# TEK-8x8.net
KiCad netlist of a schematic drawn in EAGLE
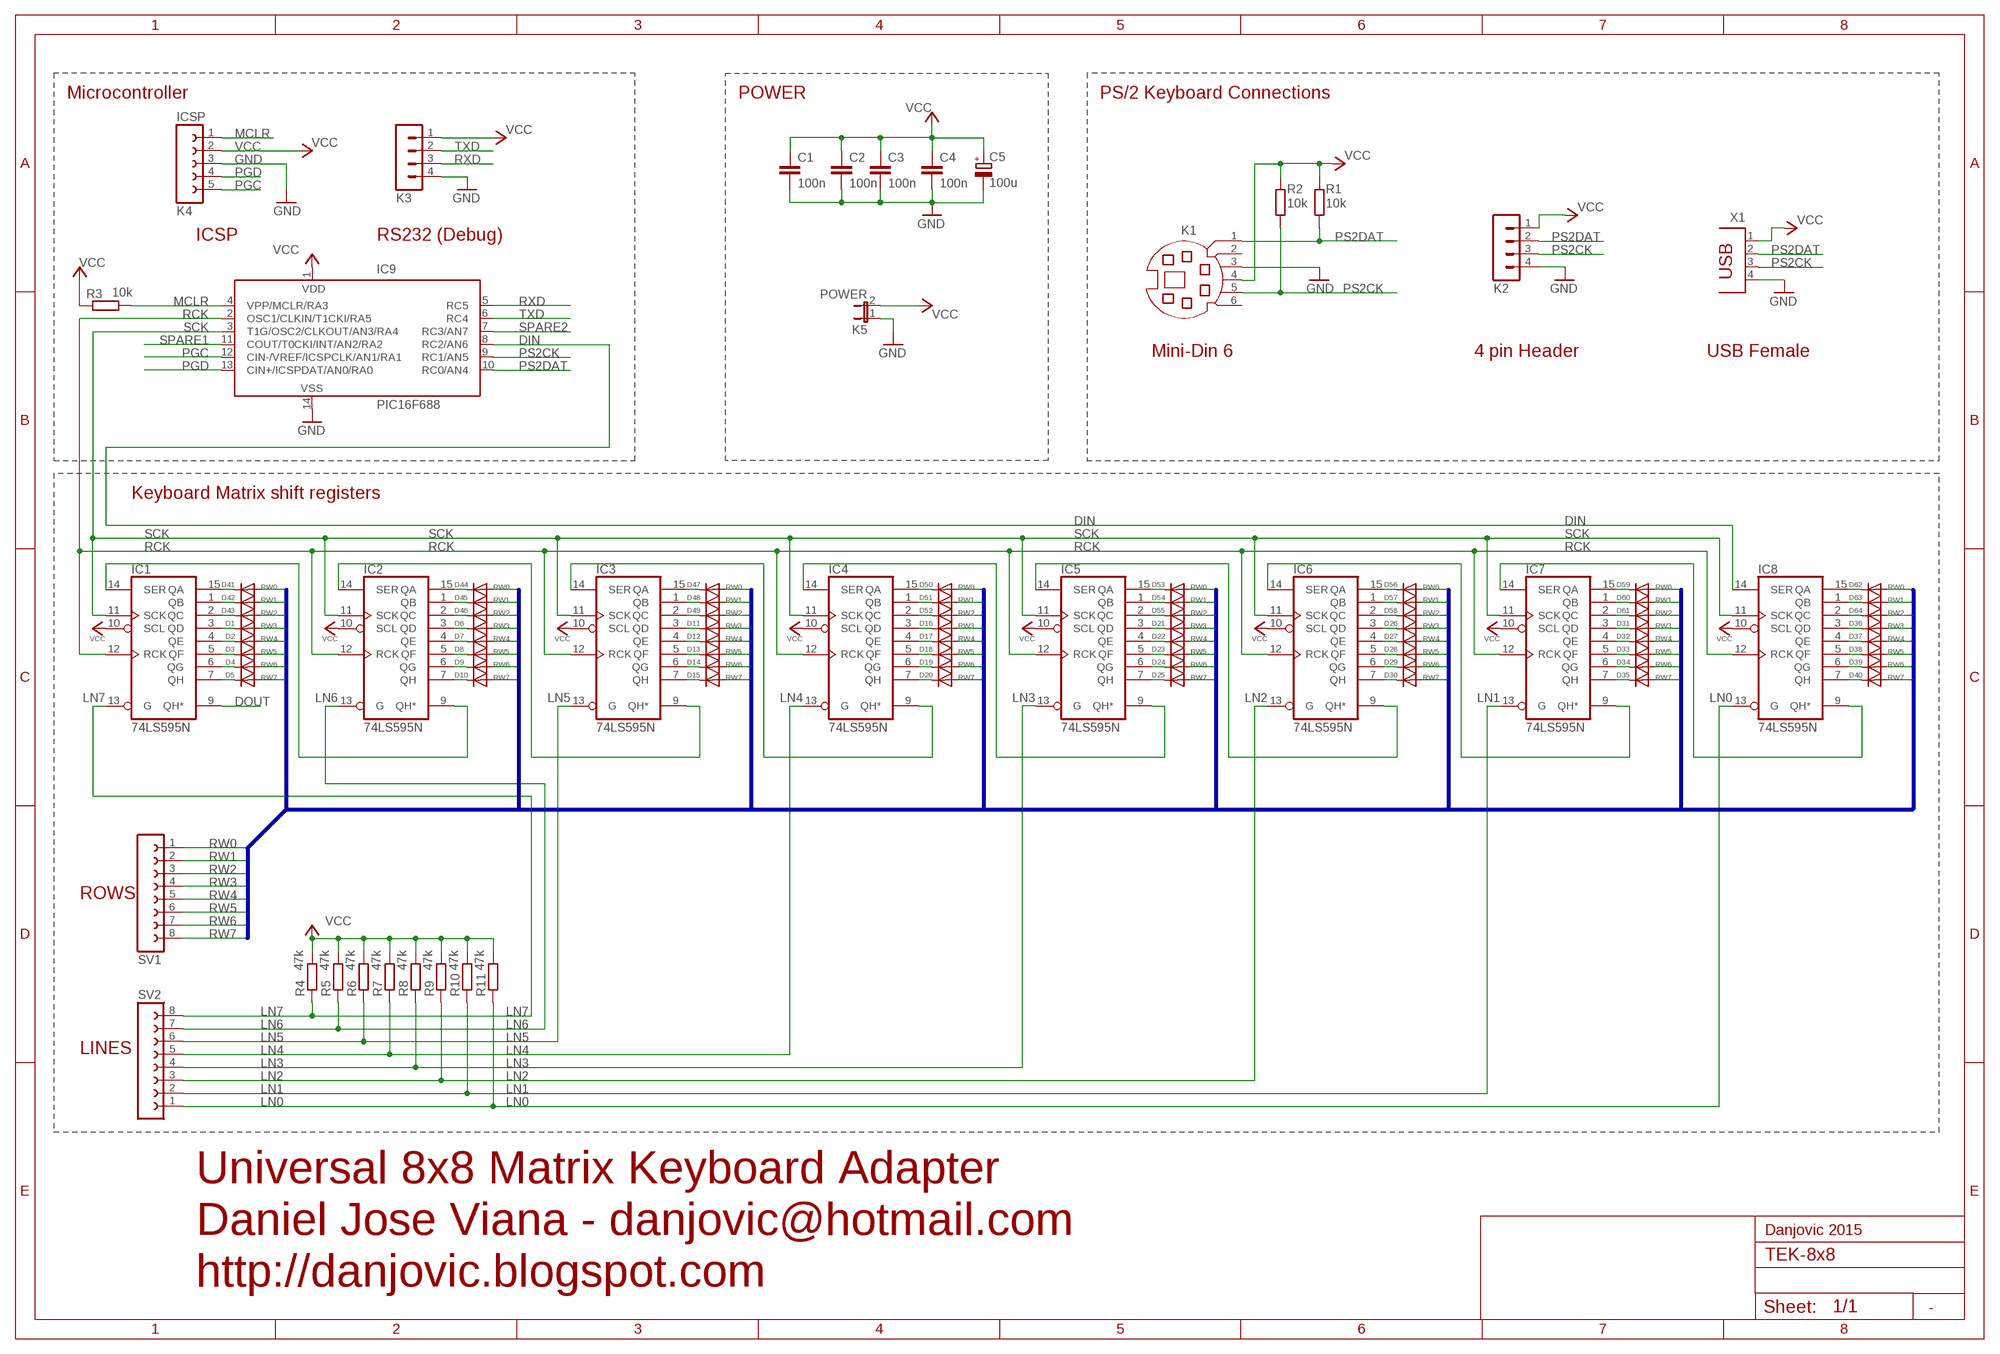
[diagram p0: schematic, sheet 1]

(export (version "E")
  (design (tool "Eeschema 10.0.6"))
  (components
    (comp (ref "C1")
      (value "100n")
      (footprint "eagle-import:C050-030X075")
      (libsource (lib "eagle-import") (part "C-EU050-030X075"))
    )
    (comp (ref "C2")
      (value "100n")
      (footprint "eagle-import:C050-030X075")
      (libsource (lib "eagle-import") (part "C-EU050-030X075"))
    )
    (comp (ref "C3")
      (value "100n")
      (footprint "eagle-import:C050-030X075")
      (libsource (lib "eagle-import") (part "C-EU050-030X075"))
    )
    (comp (ref "C4")
      (value "100n")
      (footprint "eagle-import:C050-030X075")
      (libsource (lib "eagle-import") (part "C-EU050-030X075"))
    )
    (comp (ref "C5")
      (value "100u")
      (footprint "eagle-import:E3,5-10")
      (libsource (lib "eagle-import") (part "CPOL-EUE3.5-10"))
    )
    (comp (ref "D1")
      (value "DIODE-D-2.5")
      (footprint "eagle-import:D-2.5")
      (libsource (lib "eagle-import") (part "DIODE-D-2.5"))
    )
    (comp (ref "D2")
      (value "DIODE-D-2.5")
      (footprint "eagle-import:D-2.5")
      (libsource (lib "eagle-import") (part "DIODE-D-2.5"))
    )
    (comp (ref "D3")
      (value "DIODE-D-2.5")
      (footprint "eagle-import:D-2.5")
      (libsource (lib "eagle-import") (part "DIODE-D-2.5"))
    )
    (comp (ref "D4")
      (value "DIODE-D-2.5")
      (footprint "eagle-import:D-2.5")
      (libsource (lib "eagle-import") (part "DIODE-D-2.5"))
    )
    (comp (ref "D5")
      (value "DIODE-D-2.5")
      (footprint "eagle-import:D-2.5")
      (libsource (lib "eagle-import") (part "DIODE-D-2.5"))
    )
    (comp (ref "D6")
      (value "DIODE-D-2.5")
      (footprint "eagle-import:D-2.5")
      (libsource (lib "eagle-import") (part "DIODE-D-2.5"))
    )
    (comp (ref "D7")
      (value "DIODE-D-2.5")
      (footprint "eagle-import:D-2.5")
      (libsource (lib "eagle-import") (part "DIODE-D-2.5"))
    )
    (comp (ref "D8")
      (value "DIODE-D-2.5")
      (footprint "eagle-import:D-2.5")
      (libsource (lib "eagle-import") (part "DIODE-D-2.5"))
    )
    (comp (ref "D9")
      (value "DIODE-D-2.5")
      (footprint "eagle-import:D-2.5")
      (libsource (lib "eagle-import") (part "DIODE-D-2.5"))
    )
    (comp (ref "D10")
      (value "DIODE-D-2.5")
      (footprint "eagle-import:D-2.5")
      (libsource (lib "eagle-import") (part "DIODE-D-2.5"))
    )
    (comp (ref "D11")
      (value "DIODE-D-2.5")
      (footprint "eagle-import:D-2.5")
      (libsource (lib "eagle-import") (part "DIODE-D-2.5"))
    )
    (comp (ref "D12")
      (value "DIODE-D-2.5")
      (footprint "eagle-import:D-2.5")
      (libsource (lib "eagle-import") (part "DIODE-D-2.5"))
    )
    (comp (ref "D13")
      (value "DIODE-D-2.5")
      (footprint "eagle-import:D-2.5")
      (libsource (lib "eagle-import") (part "DIODE-D-2.5"))
    )
    (comp (ref "D14")
      (value "DIODE-D-2.5")
      (footprint "eagle-import:D-2.5")
      (libsource (lib "eagle-import") (part "DIODE-D-2.5"))
    )
    (comp (ref "D15")
      (value "DIODE-D-2.5")
      (footprint "eagle-import:D-2.5")
      (libsource (lib "eagle-import") (part "DIODE-D-2.5"))
    )
    (comp (ref "D16")
      (value "DIODE-D-2.5")
      (footprint "eagle-import:D-2.5")
      (libsource (lib "eagle-import") (part "DIODE-D-2.5"))
    )
    (comp (ref "D17")
      (value "DIODE-D-2.5")
      (footprint "eagle-import:D-2.5")
      (libsource (lib "eagle-import") (part "DIODE-D-2.5"))
    )
    (comp (ref "D18")
      (value "DIODE-D-2.5")
      (footprint "eagle-import:D-2.5")
      (libsource (lib "eagle-import") (part "DIODE-D-2.5"))
    )
    (comp (ref "D19")
      (value "DIODE-D-2.5")
      (footprint "eagle-import:D-2.5")
      (libsource (lib "eagle-import") (part "DIODE-D-2.5"))
    )
    (comp (ref "D20")
      (value "DIODE-D-2.5")
      (footprint "eagle-import:D-2.5")
      (libsource (lib "eagle-import") (part "DIODE-D-2.5"))
    )
    (comp (ref "D21")
      (value "DIODE-D-2.5")
      (footprint "eagle-import:D-2.5")
      (libsource (lib "eagle-import") (part "DIODE-D-2.5"))
    )
    (comp (ref "D22")
      (value "DIODE-D-2.5")
      (footprint "eagle-import:D-2.5")
      (libsource (lib "eagle-import") (part "DIODE-D-2.5"))
    )
    (comp (ref "D23")
      (value "DIODE-D-2.5")
      (footprint "eagle-import:D-2.5")
      (libsource (lib "eagle-import") (part "DIODE-D-2.5"))
    )
    (comp (ref "D24")
      (value "DIODE-D-2.5")
      (footprint "eagle-import:D-2.5")
      (libsource (lib "eagle-import") (part "DIODE-D-2.5"))
    )
    (comp (ref "D25")
      (value "DIODE-D-2.5")
      (footprint "eagle-import:D-2.5")
      (libsource (lib "eagle-import") (part "DIODE-D-2.5"))
    )
    (comp (ref "D26")
      (value "DIODE-D-2.5")
      (footprint "eagle-import:D-2.5")
      (libsource (lib "eagle-import") (part "DIODE-D-2.5"))
    )
    (comp (ref "D27")
      (value "DIODE-D-2.5")
      (footprint "eagle-import:D-2.5")
      (libsource (lib "eagle-import") (part "DIODE-D-2.5"))
    )
    (comp (ref "D28")
      (value "DIODE-D-2.5")
      (footprint "eagle-import:D-2.5")
      (libsource (lib "eagle-import") (part "DIODE-D-2.5"))
    )
    (comp (ref "D29")
      (value "DIODE-D-2.5")
      (footprint "eagle-import:D-2.5")
      (libsource (lib "eagle-import") (part "DIODE-D-2.5"))
    )
    (comp (ref "D30")
      (value "DIODE-D-2.5")
      (footprint "eagle-import:D-2.5")
      (libsource (lib "eagle-import") (part "DIODE-D-2.5"))
    )
    (comp (ref "D31")
      (value "DIODE-D-2.5")
      (footprint "eagle-import:D-2.5")
      (libsource (lib "eagle-import") (part "DIODE-D-2.5"))
    )
    (comp (ref "D32")
      (value "DIODE-D-2.5")
      (footprint "eagle-import:D-2.5")
      (libsource (lib "eagle-import") (part "DIODE-D-2.5"))
    )
    (comp (ref "D33")
      (value "DIODE-D-2.5")
      (footprint "eagle-import:D-2.5")
      (libsource (lib "eagle-import") (part "DIODE-D-2.5"))
    )
    (comp (ref "D34")
      (value "DIODE-D-2.5")
      (footprint "eagle-import:D-2.5")
      (libsource (lib "eagle-import") (part "DIODE-D-2.5"))
    )
    (comp (ref "D35")
      (value "DIODE-D-2.5")
      (footprint "eagle-import:D-2.5")
      (libsource (lib "eagle-import") (part "DIODE-D-2.5"))
    )
    (comp (ref "D36")
      (value "DIODE-D-2.5")
      (footprint "eagle-import:D-2.5")
      (libsource (lib "eagle-import") (part "DIODE-D-2.5"))
    )
    (comp (ref "D37")
      (value "DIODE-D-2.5")
      (footprint "eagle-import:D-2.5")
      (libsource (lib "eagle-import") (part "DIODE-D-2.5"))
    )
    (comp (ref "D38")
      (value "DIODE-D-2.5")
      (footprint "eagle-import:D-2.5")
      (libsource (lib "eagle-import") (part "DIODE-D-2.5"))
    )
    (comp (ref "D39")
      (value "DIODE-D-2.5")
      (footprint "eagle-import:D-2.5")
      (libsource (lib "eagle-import") (part "DIODE-D-2.5"))
    )
    (comp (ref "D40")
      (value "DIODE-D-2.5")
      (footprint "eagle-import:D-2.5")
      (libsource (lib "eagle-import") (part "DIODE-D-2.5"))
    )
    (comp (ref "D41")
      (value "DIODE-D-2.5")
      (footprint "eagle-import:D-2.5")
      (libsource (lib "eagle-import") (part "DIODE-D-2.5"))
    )
    (comp (ref "D42")
      (value "DIODE-D-2.5")
      (footprint "eagle-import:D-2.5")
      (libsource (lib "eagle-import") (part "DIODE-D-2.5"))
    )
    (comp (ref "D43")
      (value "DIODE-D-2.5")
      (footprint "eagle-import:D-2.5")
      (libsource (lib "eagle-import") (part "DIODE-D-2.5"))
    )
    (comp (ref "D44")
      (value "DIODE-D-2.5")
      (footprint "eagle-import:D-2.5")
      (libsource (lib "eagle-import") (part "DIODE-D-2.5"))
    )
    (comp (ref "D45")
      (value "DIODE-D-2.5")
      (footprint "eagle-import:D-2.5")
      (libsource (lib "eagle-import") (part "DIODE-D-2.5"))
    )
    (comp (ref "D46")
      (value "DIODE-D-2.5")
      (footprint "eagle-import:D-2.5")
      (libsource (lib "eagle-import") (part "DIODE-D-2.5"))
    )
    (comp (ref "D47")
      (value "DIODE-D-2.5")
      (footprint "eagle-import:D-2.5")
      (libsource (lib "eagle-import") (part "DIODE-D-2.5"))
    )
    (comp (ref "D48")
      (value "DIODE-D-2.5")
      (footprint "eagle-import:D-2.5")
      (libsource (lib "eagle-import") (part "DIODE-D-2.5"))
    )
    (comp (ref "D49")
      (value "DIODE-D-2.5")
      (footprint "eagle-import:D-2.5")
      (libsource (lib "eagle-import") (part "DIODE-D-2.5"))
    )
    (comp (ref "D50")
      (value "DIODE-D-2.5")
      (footprint "eagle-import:D-2.5")
      (libsource (lib "eagle-import") (part "DIODE-D-2.5"))
    )
    (comp (ref "D51")
      (value "DIODE-D-2.5")
      (footprint "eagle-import:D-2.5")
      (libsource (lib "eagle-import") (part "DIODE-D-2.5"))
    )
    (comp (ref "D52")
      (value "DIODE-D-2.5")
      (footprint "eagle-import:D-2.5")
      (libsource (lib "eagle-import") (part "DIODE-D-2.5"))
    )
    (comp (ref "D53")
      (value "DIODE-D-2.5")
      (footprint "eagle-import:D-2.5")
      (libsource (lib "eagle-import") (part "DIODE-D-2.5"))
    )
    (comp (ref "D54")
      (value "DIODE-D-2.5")
      (footprint "eagle-import:D-2.5")
      (libsource (lib "eagle-import") (part "DIODE-D-2.5"))
    )
    (comp (ref "D55")
      (value "DIODE-D-2.5")
      (footprint "eagle-import:D-2.5")
      (libsource (lib "eagle-import") (part "DIODE-D-2.5"))
    )
    (comp (ref "D56")
      (value "DIODE-D-2.5")
      (footprint "eagle-import:D-2.5")
      (libsource (lib "eagle-import") (part "DIODE-D-2.5"))
    )
    (comp (ref "D57")
      (value "DIODE-D-2.5")
      (footprint "eagle-import:D-2.5")
      (libsource (lib "eagle-import") (part "DIODE-D-2.5"))
    )
    (comp (ref "D58")
      (value "DIODE-D-2.5")
      (footprint "eagle-import:D-2.5")
      (libsource (lib "eagle-import") (part "DIODE-D-2.5"))
    )
    (comp (ref "D59")
      (value "DIODE-D-2.5")
      (footprint "eagle-import:D-2.5")
      (libsource (lib "eagle-import") (part "DIODE-D-2.5"))
    )
    (comp (ref "D60")
      (value "DIODE-D-2.5")
      (footprint "eagle-import:D-2.5")
      (libsource (lib "eagle-import") (part "DIODE-D-2.5"))
    )
    (comp (ref "D61")
      (value "DIODE-D-2.5")
      (footprint "eagle-import:D-2.5")
      (libsource (lib "eagle-import") (part "DIODE-D-2.5"))
    )
    (comp (ref "D62")
      (value "DIODE-D-2.5")
      (footprint "eagle-import:D-2.5")
      (libsource (lib "eagle-import") (part "DIODE-D-2.5"))
    )
    (comp (ref "D63")
      (value "DIODE-D-2.5")
      (footprint "eagle-import:D-2.5")
      (libsource (lib "eagle-import") (part "DIODE-D-2.5"))
    )
    (comp (ref "D64")
      (value "DIODE-D-2.5")
      (footprint "eagle-import:D-2.5")
      (libsource (lib "eagle-import") (part "DIODE-D-2.5"))
    )
    (comp (ref "IC1")
      (value "74LS595N")
      (footprint "eagle-import:DIL16")
      (libsource (lib "eagle-import") (part "74595NLS"))
    )
    (comp (ref "IC2")
      (value "74LS595N")
      (footprint "eagle-import:DIL16")
      (libsource (lib "eagle-import") (part "74595NLS"))
    )
    (comp (ref "IC3")
      (value "74LS595N")
      (footprint "eagle-import:DIL16")
      (libsource (lib "eagle-import") (part "74595NLS"))
    )
    (comp (ref "IC4")
      (value "74LS595N")
      (footprint "eagle-import:DIL16")
      (libsource (lib "eagle-import") (part "74595NLS"))
    )
    (comp (ref "IC5")
      (value "74LS595N")
      (footprint "eagle-import:DIL16")
      (libsource (lib "eagle-import") (part "74595NLS"))
    )
    (comp (ref "IC6")
      (value "74LS595N")
      (footprint "eagle-import:DIL16")
      (libsource (lib "eagle-import") (part "74595NLS"))
    )
    (comp (ref "IC7")
      (value "74LS595N")
      (footprint "eagle-import:DIL16")
      (libsource (lib "eagle-import") (part "74595NLS"))
    )
    (comp (ref "IC8")
      (value "74LS595N")
      (footprint "eagle-import:DIL16")
      (libsource (lib "eagle-import") (part "74595NLS"))
    )
    (comp (ref "IC9")
      (value "PIC16F688")
      (footprint "eagle-import:DIL14")
      (fields (field (name "MF") "MICROCHIP") (field (name "MPN") "PIC16F676-I/P"))
      (libsource (lib "eagle-import") (part "PIC16F676P"))
    )
    (comp (ref "K1")
      (value "MD06SS")
      (footprint "eagle-import:MDIN06SS")
      (libsource (lib "eagle-import") (part "MD06SS"))
    )
    (comp (ref "K2")
      (value "MA04-1")
      (footprint "eagle-import:MA04-1")
      (libsource (lib "eagle-import") (part "MA04-1"))
    )
    (comp (ref "K3")
      (value "MA04-1")
      (footprint "eagle-import:MA04-1")
      (libsource (lib "eagle-import") (part "MA04-1"))
    )
    (comp (ref "K4")
      (value "ICSP")
      (footprint "eagle-import:FE05-1")
      (libsource (lib "eagle-import") (part "FE05-1"))
    )
    (comp (ref "K5")
      (value "POWER")
      (footprint "eagle-import:JP1")
      (libsource (lib "eagle-import") (part "JP1E"))
    )
    (comp (ref "R1")
      (value "10k")
      (footprint "eagle-import:0204_7")
      (libsource (lib "eagle-import") (part "R-EU_0204/7"))
    )
    (comp (ref "R2")
      (value "10k")
      (footprint "eagle-import:0204_7")
      (libsource (lib "eagle-import") (part "R-EU_0204/7"))
    )
    (comp (ref "R3")
      (value "10k")
      (footprint "eagle-import:0204_7")
      (libsource (lib "eagle-import") (part "R-EU_0204/7"))
    )
    (comp (ref "R4")
      (value "47k")
      (footprint "eagle-import:0204_7")
      (libsource (lib "eagle-import") (part "R-EU_0204/7"))
    )
    (comp (ref "R5")
      (value "47k")
      (footprint "eagle-import:0204_7")
      (libsource (lib "eagle-import") (part "R-EU_0204/7"))
    )
    (comp (ref "R6")
      (value "47k")
      (footprint "eagle-import:0204_7")
      (libsource (lib "eagle-import") (part "R-EU_0204/7"))
    )
    (comp (ref "R7")
      (value "47k")
      (footprint "eagle-import:0204_7")
      (libsource (lib "eagle-import") (part "R-EU_0204/7"))
    )
    (comp (ref "R8")
      (value "47k")
      (footprint "eagle-import:0204_7")
      (libsource (lib "eagle-import") (part "R-EU_0204/7"))
    )
    (comp (ref "R9")
      (value "47k")
      (footprint "eagle-import:0204_7")
      (libsource (lib "eagle-import") (part "R-EU_0204/7"))
    )
    (comp (ref "R10")
      (value "47k")
      (footprint "eagle-import:0204_7")
      (libsource (lib "eagle-import") (part "R-EU_0204/7"))
    )
    (comp (ref "R11")
      (value "47k")
      (footprint "eagle-import:0204_7")
      (libsource (lib "eagle-import") (part "R-EU_0204/7"))
    )
    (comp (ref "SV1")
      (value "FE08-1")
      (footprint "eagle-import:FE08")
      (libsource (lib "eagle-import") (part "FE08-1"))
    )
    (comp (ref "SV2")
      (value "FE08-1")
      (footprint "eagle-import:FE08")
      (libsource (lib "eagle-import") (part "FE08-1"))
    )
    (comp (ref "X1")
      (value "PN87520")
      (footprint "eagle-import:PN87520")
      (libsource (lib "eagle-import") (part "PN87520"))
    )
  )
  (nets
    (net (code "1") (name "/DIN") (class "Default")
      (node (ref "IC8") (pin "14") (pinfunction "SER_14") (pintype "input"))
      (node (ref "IC9") (pin "8") (pinfunction "RC2/AN6_8") (pintype "bidirectional"))
    )
    (net (code "2") (name "/DOUT") (class "Default")
      (node (ref "IC1") (pin "9") (pinfunction "QH*_9") (pintype "tri_state"))
    )
    (net (code "3") (name "/LN0") (class "Default")
      (node (ref "IC8") (pin "13") (pinfunction "G_13") (pintype "input"))
      (node (ref "R11") (pin "1") (pinfunction "1_1") (pintype "passive"))
      (node (ref "SV2") (pin "1") (pinfunction "1_1") (pintype "passive"))
    )
    (net (code "4") (name "/LN1") (class "Default")
      (node (ref "IC7") (pin "13") (pinfunction "G_13") (pintype "input"))
      (node (ref "R10") (pin "1") (pinfunction "1_1") (pintype "passive"))
      (node (ref "SV2") (pin "2") (pinfunction "2_2") (pintype "passive"))
    )
    (net (code "5") (name "/LN2") (class "Default")
      (node (ref "IC6") (pin "13") (pinfunction "G_13") (pintype "input"))
      (node (ref "R9") (pin "1") (pinfunction "1_1") (pintype "passive"))
      (node (ref "SV2") (pin "3") (pinfunction "3_3") (pintype "passive"))
    )
    (net (code "6") (name "/LN3") (class "Default")
      (node (ref "IC5") (pin "13") (pinfunction "G_13") (pintype "input"))
      (node (ref "R8") (pin "1") (pinfunction "1_1") (pintype "passive"))
      (node (ref "SV2") (pin "4") (pinfunction "4_4") (pintype "passive"))
    )
    (net (code "7") (name "/LN4") (class "Default")
      (node (ref "IC4") (pin "13") (pinfunction "G_13") (pintype "input"))
      (node (ref "R7") (pin "1") (pinfunction "1_1") (pintype "passive"))
      (node (ref "SV2") (pin "5") (pinfunction "5_5") (pintype "passive"))
    )
    (net (code "8") (name "/LN5") (class "Default")
      (node (ref "IC3") (pin "13") (pinfunction "G_13") (pintype "input"))
      (node (ref "R6") (pin "1") (pinfunction "1_1") (pintype "passive"))
      (node (ref "SV2") (pin "6") (pinfunction "6_6") (pintype "passive"))
    )
    (net (code "9") (name "/LN6") (class "Default")
      (node (ref "IC2") (pin "13") (pinfunction "G_13") (pintype "input"))
      (node (ref "R5") (pin "1") (pinfunction "1_1") (pintype "passive"))
      (node (ref "SV2") (pin "7") (pinfunction "7_7") (pintype "passive"))
    )
    (net (code "10") (name "/LN7") (class "Default")
      (node (ref "IC1") (pin "13") (pinfunction "G_13") (pintype "input"))
      (node (ref "R4") (pin "1") (pinfunction "1_1") (pintype "passive"))
      (node (ref "SV2") (pin "8") (pinfunction "8_8") (pintype "passive"))
    )
    (net (code "11") (name "/MCLR") (class "Default")
      (node (ref "IC9") (pin "4") (pinfunction "VPP/MCLR/RA3_4") (pintype "input"))
      (node (ref "K4") (pin "1") (pinfunction "1_1") (pintype "passive"))
      (node (ref "R3") (pin "1") (pinfunction "1_1") (pintype "passive"))
    )
    (net (code "12") (name "/PGC") (class "Default")
      (node (ref "IC9") (pin "12") (pinfunction "CIN-/VREF/ICSPCLK/AN1/RA1_12") (pintype "bidirectional"))
      (node (ref "K4") (pin "5") (pinfunction "5_5") (pintype "passive"))
    )
    (net (code "13") (name "/PGD") (class "Default")
      (node (ref "IC9") (pin "13") (pinfunction "CIN+/ICSPDAT/AN0/RA0_13") (pintype "bidirectional"))
      (node (ref "K4") (pin "4") (pinfunction "4_4") (pintype "passive"))
    )
    (net (code "14") (name "/PS2CK") (class "Default")
      (node (ref "IC9") (pin "9") (pinfunction "RC1/AN5_9") (pintype "bidirectional"))
      (node (ref "K1") (pin "5") (pinfunction "5_5") (pintype "passive"))
      (node (ref "K2") (pin "3") (pinfunction "3_3") (pintype "passive"))
      (node (ref "R2") (pin "1") (pinfunction "1_1") (pintype "passive"))
      (node (ref "X1") (pin "3") (pinfunction "3_3") (pintype "passive"))
    )
    (net (code "15") (name "/PS2DAT") (class "Default")
      (node (ref "IC9") (pin "10") (pinfunction "RC0/AN4_10") (pintype "bidirectional"))
      (node (ref "K1") (pin "1") (pinfunction "1_1") (pintype "passive"))
      (node (ref "K2") (pin "2") (pinfunction "2_2") (pintype "passive"))
      (node (ref "R1") (pin "1") (pinfunction "1_1") (pintype "passive"))
      (node (ref "X1") (pin "2") (pinfunction "2_2") (pintype "passive"))
    )
    (net (code "16") (name "/RCK") (class "Default")
      (node (ref "IC1") (pin "12") (pinfunction "RCK_12") (pintype "input"))
      (node (ref "IC2") (pin "12") (pinfunction "RCK_12") (pintype "input"))
      (node (ref "IC3") (pin "12") (pinfunction "RCK_12") (pintype "input"))
      (node (ref "IC4") (pin "12") (pinfunction "RCK_12") (pintype "input"))
      (node (ref "IC5") (pin "12") (pinfunction "RCK_12") (pintype "input"))
      (node (ref "IC6") (pin "12") (pinfunction "RCK_12") (pintype "input"))
      (node (ref "IC7") (pin "12") (pinfunction "RCK_12") (pintype "input"))
      (node (ref "IC8") (pin "12") (pinfunction "RCK_12") (pintype "input"))
      (node (ref "IC9") (pin "2") (pinfunction "OSC1/CLKIN/T1CKI/RA5_2") (pintype "bidirectional"))
    )
    (net (code "17") (name "/RW0") (class "Default")
      (node (ref "D41") (pin "A") (pinfunction "A_A") (pintype "passive"))
      (node (ref "D44") (pin "A") (pinfunction "A_A") (pintype "passive"))
      (node (ref "D47") (pin "A") (pinfunction "A_A") (pintype "passive"))
      (node (ref "D50") (pin "A") (pinfunction "A_A") (pintype "passive"))
      (node (ref "D53") (pin "A") (pinfunction "A_A") (pintype "passive"))
      (node (ref "D56") (pin "A") (pinfunction "A_A") (pintype "passive"))
      (node (ref "D59") (pin "A") (pinfunction "A_A") (pintype "passive"))
      (node (ref "D62") (pin "A") (pinfunction "A_A") (pintype "passive"))
      (node (ref "SV1") (pin "1") (pinfunction "1_1") (pintype "passive"))
    )
    (net (code "18") (name "/RW1") (class "Default")
      (node (ref "D42") (pin "A") (pinfunction "A_A") (pintype "passive"))
      (node (ref "D45") (pin "A") (pinfunction "A_A") (pintype "passive"))
      (node (ref "D48") (pin "A") (pinfunction "A_A") (pintype "passive"))
      (node (ref "D51") (pin "A") (pinfunction "A_A") (pintype "passive"))
      (node (ref "D54") (pin "A") (pinfunction "A_A") (pintype "passive"))
      (node (ref "D57") (pin "A") (pinfunction "A_A") (pintype "passive"))
      (node (ref "D60") (pin "A") (pinfunction "A_A") (pintype "passive"))
      (node (ref "D63") (pin "A") (pinfunction "A_A") (pintype "passive"))
      (node (ref "SV1") (pin "2") (pinfunction "2_2") (pintype "passive"))
    )
    (net (code "19") (name "/RW2") (class "Default")
      (node (ref "D43") (pin "A") (pinfunction "A_A") (pintype "passive"))
      (node (ref "D46") (pin "A") (pinfunction "A_A") (pintype "passive"))
      (node (ref "D49") (pin "A") (pinfunction "A_A") (pintype "passive"))
      (node (ref "D52") (pin "A") (pinfunction "A_A") (pintype "passive"))
      (node (ref "D55") (pin "A") (pinfunction "A_A") (pintype "passive"))
      (node (ref "D58") (pin "A") (pinfunction "A_A") (pintype "passive"))
      (node (ref "D61") (pin "A") (pinfunction "A_A") (pintype "passive"))
      (node (ref "D64") (pin "A") (pinfunction "A_A") (pintype "passive"))
      (node (ref "SV1") (pin "3") (pinfunction "3_3") (pintype "passive"))
    )
    (net (code "20") (name "/RW3") (class "Default")
      (node (ref "D1") (pin "A") (pinfunction "A_A") (pintype "passive"))
      (node (ref "D11") (pin "A") (pinfunction "A_A") (pintype "passive"))
      (node (ref "D16") (pin "A") (pinfunction "A_A") (pintype "passive"))
      (node (ref "D21") (pin "A") (pinfunction "A_A") (pintype "passive"))
      (node (ref "D26") (pin "A") (pinfunction "A_A") (pintype "passive"))
      (node (ref "D31") (pin "A") (pinfunction "A_A") (pintype "passive"))
      (node (ref "D36") (pin "A") (pinfunction "A_A") (pintype "passive"))
      (node (ref "D6") (pin "A") (pinfunction "A_A") (pintype "passive"))
      (node (ref "SV1") (pin "4") (pinfunction "4_4") (pintype "passive"))
    )
    (net (code "21") (name "/RW4") (class "Default")
      (node (ref "D12") (pin "A") (pinfunction "A_A") (pintype "passive"))
      (node (ref "D17") (pin "A") (pinfunction "A_A") (pintype "passive"))
      (node (ref "D2") (pin "A") (pinfunction "A_A") (pintype "passive"))
      (node (ref "D22") (pin "A") (pinfunction "A_A") (pintype "passive"))
      (node (ref "D27") (pin "A") (pinfunction "A_A") (pintype "passive"))
      (node (ref "D32") (pin "A") (pinfunction "A_A") (pintype "passive"))
      (node (ref "D37") (pin "A") (pinfunction "A_A") (pintype "passive"))
      (node (ref "D7") (pin "A") (pinfunction "A_A") (pintype "passive"))
      (node (ref "SV1") (pin "5") (pinfunction "5_5") (pintype "passive"))
    )
    (net (code "22") (name "/RW5") (class "Default")
      (node (ref "D13") (pin "A") (pinfunction "A_A") (pintype "passive"))
      (node (ref "D18") (pin "A") (pinfunction "A_A") (pintype "passive"))
      (node (ref "D23") (pin "A") (pinfunction "A_A") (pintype "passive"))
      (node (ref "D28") (pin "A") (pinfunction "A_A") (pintype "passive"))
      (node (ref "D3") (pin "A") (pinfunction "A_A") (pintype "passive"))
      (node (ref "D33") (pin "A") (pinfunction "A_A") (pintype "passive"))
      (node (ref "D38") (pin "A") (pinfunction "A_A") (pintype "passive"))
      (node (ref "D8") (pin "A") (pinfunction "A_A") (pintype "passive"))
      (node (ref "SV1") (pin "6") (pinfunction "6_6") (pintype "passive"))
    )
    (net (code "23") (name "/RW6") (class "Default")
      (node (ref "D14") (pin "A") (pinfunction "A_A") (pintype "passive"))
      (node (ref "D19") (pin "A") (pinfunction "A_A") (pintype "passive"))
      (node (ref "D24") (pin "A") (pinfunction "A_A") (pintype "passive"))
      (node (ref "D29") (pin "A") (pinfunction "A_A") (pintype "passive"))
      (node (ref "D34") (pin "A") (pinfunction "A_A") (pintype "passive"))
      (node (ref "D39") (pin "A") (pinfunction "A_A") (pintype "passive"))
      (node (ref "D4") (pin "A") (pinfunction "A_A") (pintype "passive"))
      (node (ref "D9") (pin "A") (pinfunction "A_A") (pintype "passive"))
      (node (ref "SV1") (pin "7") (pinfunction "7_7") (pintype "passive"))
    )
    (net (code "24") (name "/RW7") (class "Default")
      (node (ref "D10") (pin "A") (pinfunction "A_A") (pintype "passive"))
      (node (ref "D15") (pin "A") (pinfunction "A_A") (pintype "passive"))
      (node (ref "D20") (pin "A") (pinfunction "A_A") (pintype "passive"))
      (node (ref "D25") (pin "A") (pinfunction "A_A") (pintype "passive"))
      (node (ref "D30") (pin "A") (pinfunction "A_A") (pintype "passive"))
      (node (ref "D35") (pin "A") (pinfunction "A_A") (pintype "passive"))
      (node (ref "D40") (pin "A") (pinfunction "A_A") (pintype "passive"))
      (node (ref "D5") (pin "A") (pinfunction "A_A") (pintype "passive"))
      (node (ref "SV1") (pin "8") (pinfunction "8_8") (pintype "passive"))
    )
    (net (code "25") (name "/RXD") (class "Default")
      (node (ref "IC9") (pin "5") (pinfunction "RC5_5") (pintype "bidirectional"))
      (node (ref "K3") (pin "3") (pinfunction "3_3") (pintype "passive"))
    )
    (net (code "26") (name "/SCK") (class "Default")
      (node (ref "IC1") (pin "11") (pinfunction "SCK_11") (pintype "input"))
      (node (ref "IC2") (pin "11") (pinfunction "SCK_11") (pintype "input"))
      (node (ref "IC3") (pin "11") (pinfunction "SCK_11") (pintype "input"))
      (node (ref "IC4") (pin "11") (pinfunction "SCK_11") (pintype "input"))
      (node (ref "IC5") (pin "11") (pinfunction "SCK_11") (pintype "input"))
      (node (ref "IC6") (pin "11") (pinfunction "SCK_11") (pintype "input"))
      (node (ref "IC7") (pin "11") (pinfunction "SCK_11") (pintype "input"))
      (node (ref "IC8") (pin "11") (pinfunction "SCK_11") (pintype "input"))
      (node (ref "IC9") (pin "3") (pinfunction "T1G/OSC2/CLKOUT/AN3/RA4_3") (pintype "bidirectional"))
    )
    (net (code "27") (name "/SPARE1") (class "Default")
      (node (ref "IC9") (pin "11") (pinfunction "COUT/T0CKI/INT/AN2/RA2_11") (pintype "bidirectional"))
    )
    (net (code "28") (name "/SPARE2") (class "Default")
      (node (ref "IC9") (pin "7") (pinfunction "RC3/AN7_7") (pintype "bidirectional"))
    )
    (net (code "29") (name "/TXD") (class "Default")
      (node (ref "IC9") (pin "6") (pinfunction "RC4_6") (pintype "bidirectional"))
      (node (ref "K3") (pin "2") (pinfunction "2_2") (pintype "passive"))
    )
    (net (code "30") (name "GND") (class "Default")
      (node (ref "C1") (pin "2") (pinfunction "2_2") (pintype "passive"))
      (node (ref "C2") (pin "2") (pinfunction "2_2") (pintype "passive"))
      (node (ref "C3") (pin "2") (pinfunction "2_2") (pintype "passive"))
      (node (ref "C4") (pin "2") (pinfunction "2_2") (pintype "passive"))
      (node (ref "C5") (pin "-") (pinfunction "-_-") (pintype "passive"))
      (node (ref "IC9") (pin "14") (pinfunction "VSS_14") (pintype "power_in"))
      (node (ref "K1") (pin "3") (pinfunction "3_3") (pintype "passive"))
      (node (ref "K2") (pin "4") (pinfunction "4_4") (pintype "passive"))
      (node (ref "K3") (pin "4") (pinfunction "4_4") (pintype "passive"))
      (node (ref "K4") (pin "3") (pinfunction "3_3") (pintype "passive"))
      (node (ref "K5") (pin "1") (pinfunction "1_1") (pintype "passive"))
      (node (ref "X1") (pin "4") (pinfunction "4_4") (pintype "passive"))
    )
    (net (code "31") (name "Net-(IC1A-QA)") (class "Default")
      (node (ref "D41") (pin "C") (pinfunction "C_C") (pintype "passive"))
      (node (ref "IC1") (pin "15") (pinfunction "QA_15") (pintype "tri_state"))
    )
    (net (code "32") (name "Net-(IC1A-QB)") (class "Default")
      (node (ref "D42") (pin "C") (pinfunction "C_C") (pintype "passive"))
      (node (ref "IC1") (pin "1") (pinfunction "QB_1") (pintype "tri_state"))
    )
    (net (code "33") (name "Net-(IC1A-QC)") (class "Default")
      (node (ref "D43") (pin "C") (pinfunction "C_C") (pintype "passive"))
      (node (ref "IC1") (pin "2") (pinfunction "QC_2") (pintype "tri_state"))
    )
    (net (code "34") (name "Net-(IC1A-QD)") (class "Default")
      (node (ref "D1") (pin "C") (pinfunction "C_C") (pintype "passive"))
      (node (ref "IC1") (pin "3") (pinfunction "QD_3") (pintype "tri_state"))
    )
    (net (code "35") (name "Net-(IC1A-QE)") (class "Default")
      (node (ref "D2") (pin "C") (pinfunction "C_C") (pintype "passive"))
      (node (ref "IC1") (pin "4") (pinfunction "QE_4") (pintype "tri_state"))
    )
    (net (code "36") (name "Net-(IC1A-QF)") (class "Default")
      (node (ref "D3") (pin "C") (pinfunction "C_C") (pintype "passive"))
      (node (ref "IC1") (pin "5") (pinfunction "QF_5") (pintype "tri_state"))
    )
    (net (code "37") (name "Net-(IC1A-QG)") (class "Default")
      (node (ref "D4") (pin "C") (pinfunction "C_C") (pintype "passive"))
      (node (ref "IC1") (pin "6") (pinfunction "QG_6") (pintype "tri_state"))
    )
    (net (code "38") (name "Net-(IC1A-QH)") (class "Default")
      (node (ref "D5") (pin "C") (pinfunction "C_C") (pintype "passive"))
      (node (ref "IC1") (pin "7") (pinfunction "QH_7") (pintype "tri_state"))
    )
    (net (code "39") (name "Net-(IC1A-SER)") (class "Default")
      (node (ref "IC1") (pin "14") (pinfunction "SER_14") (pintype "input"))
      (node (ref "IC2") (pin "9") (pinfunction "QH*_9") (pintype "tri_state"))
    )
    (net (code "40") (name "Net-(IC2A-QA)") (class "Default")
      (node (ref "D44") (pin "C") (pinfunction "C_C") (pintype "passive"))
      (node (ref "IC2") (pin "15") (pinfunction "QA_15") (pintype "tri_state"))
    )
    (net (code "41") (name "Net-(IC2A-QB)") (class "Default")
      (node (ref "D45") (pin "C") (pinfunction "C_C") (pintype "passive"))
      (node (ref "IC2") (pin "1") (pinfunction "QB_1") (pintype "tri_state"))
    )
    (net (code "42") (name "Net-(IC2A-QC)") (class "Default")
      (node (ref "D46") (pin "C") (pinfunction "C_C") (pintype "passive"))
      (node (ref "IC2") (pin "2") (pinfunction "QC_2") (pintype "tri_state"))
    )
    (net (code "43") (name "Net-(IC2A-QD)") (class "Default")
      (node (ref "D6") (pin "C") (pinfunction "C_C") (pintype "passive"))
      (node (ref "IC2") (pin "3") (pinfunction "QD_3") (pintype "tri_state"))
    )
    (net (code "44") (name "Net-(IC2A-QE)") (class "Default")
      (node (ref "D7") (pin "C") (pinfunction "C_C") (pintype "passive"))
      (node (ref "IC2") (pin "4") (pinfunction "QE_4") (pintype "tri_state"))
    )
    (net (code "45") (name "Net-(IC2A-QF)") (class "Default")
      (node (ref "D8") (pin "C") (pinfunction "C_C") (pintype "passive"))
      (node (ref "IC2") (pin "5") (pinfunction "QF_5") (pintype "tri_state"))
    )
    (net (code "46") (name "Net-(IC2A-QG)") (class "Default")
      (node (ref "D9") (pin "C") (pinfunction "C_C") (pintype "passive"))
      (node (ref "IC2") (pin "6") (pinfunction "QG_6") (pintype "tri_state"))
    )
    (net (code "47") (name "Net-(IC2A-QH)") (class "Default")
      (node (ref "D10") (pin "C") (pinfunction "C_C") (pintype "passive"))
      (node (ref "IC2") (pin "7") (pinfunction "QH_7") (pintype "tri_state"))
    )
    (net (code "48") (name "Net-(IC2A-SER)") (class "Default")
      (node (ref "IC2") (pin "14") (pinfunction "SER_14") (pintype "input"))
      (node (ref "IC3") (pin "9") (pinfunction "QH*_9") (pintype "tri_state"))
    )
    (net (code "49") (name "Net-(IC3A-QA)") (class "Default")
      (node (ref "D47") (pin "C") (pinfunction "C_C") (pintype "passive"))
      (node (ref "IC3") (pin "15") (pinfunction "QA_15") (pintype "tri_state"))
    )
    (net (code "50") (name "Net-(IC3A-QB)") (class "Default")
      (node (ref "D48") (pin "C") (pinfunction "C_C") (pintype "passive"))
      (node (ref "IC3") (pin "1") (pinfunction "QB_1") (pintype "tri_state"))
    )
    (net (code "51") (name "Net-(IC3A-QC)") (class "Default")
      (node (ref "D49") (pin "C") (pinfunction "C_C") (pintype "passive"))
      (node (ref "IC3") (pin "2") (pinfunction "QC_2") (pintype "tri_state"))
    )
    (net (code "52") (name "Net-(IC3A-QD)") (class "Default")
      (node (ref "D11") (pin "C") (pinfunction "C_C") (pintype "passive"))
      (node (ref "IC3") (pin "3") (pinfunction "QD_3") (pintype "tri_state"))
    )
    (net (code "53") (name "Net-(IC3A-QE)") (class "Default")
      (node (ref "D12") (pin "C") (pinfunction "C_C") (pintype "passive"))
      (node (ref "IC3") (pin "4") (pinfunction "QE_4") (pintype "tri_state"))
    )
    (net (code "54") (name "Net-(IC3A-QF)") (class "Default")
      (node (ref "D13") (pin "C") (pinfunction "C_C") (pintype "passive"))
      (node (ref "IC3") (pin "5") (pinfunction "QF_5") (pintype "tri_state"))
    )
    (net (code "55") (name "Net-(IC3A-QG)") (class "Default")
      (node (ref "D14") (pin "C") (pinfunction "C_C") (pintype "passive"))
      (node (ref "IC3") (pin "6") (pinfunction "QG_6") (pintype "tri_state"))
    )
    (net (code "56") (name "Net-(IC3A-QH)") (class "Default")
      (node (ref "D15") (pin "C") (pinfunction "C_C") (pintype "passive"))
      (node (ref "IC3") (pin "7") (pinfunction "QH_7") (pintype "tri_state"))
    )
    (net (code "57") (name "Net-(IC3A-SER)") (class "Default")
      (node (ref "IC3") (pin "14") (pinfunction "SER_14") (pintype "input"))
      (node (ref "IC4") (pin "9") (pinfunction "QH*_9") (pintype "tri_state"))
    )
    (net (code "58") (name "Net-(IC4A-QA)") (class "Default")
      (node (ref "D50") (pin "C") (pinfunction "C_C") (pintype "passive"))
      (node (ref "IC4") (pin "15") (pinfunction "QA_15") (pintype "tri_state"))
    )
    (net (code "59") (name "Net-(IC4A-QB)") (class "Default")
      (node (ref "D51") (pin "C") (pinfunction "C_C") (pintype "passive"))
      (node (ref "IC4") (pin "1") (pinfunction "QB_1") (pintype "tri_state"))
    )
    (net (code "60") (name "Net-(IC4A-QC)") (class "Default")
      (node (ref "D52") (pin "C") (pinfunction "C_C") (pintype "passive"))
      (node (ref "IC4") (pin "2") (pinfunction "QC_2") (pintype "tri_state"))
    )
    (net (code "61") (name "Net-(IC4A-QD)") (class "Default")
      (node (ref "D16") (pin "C") (pinfunction "C_C") (pintype "passive"))
      (node (ref "IC4") (pin "3") (pinfunction "QD_3") (pintype "tri_state"))
    )
    (net (code "62") (name "Net-(IC4A-QE)") (class "Default")
      (node (ref "D17") (pin "C") (pinfunction "C_C") (pintype "passive"))
      (node (ref "IC4") (pin "4") (pinfunction "QE_4") (pintype "tri_state"))
    )
    (net (code "63") (name "Net-(IC4A-QF)") (class "Default")
      (node (ref "D18") (pin "C") (pinfunction "C_C") (pintype "passive"))
      (node (ref "IC4") (pin "5") (pinfunction "QF_5") (pintype "tri_state"))
    )
    (net (code "64") (name "Net-(IC4A-QG)") (class "Default")
      (node (ref "D19") (pin "C") (pinfunction "C_C") (pintype "passive"))
      (node (ref "IC4") (pin "6") (pinfunction "QG_6") (pintype "tri_state"))
    )
    (net (code "65") (name "Net-(IC4A-QH)") (class "Default")
      (node (ref "D20") (pin "C") (pinfunction "C_C") (pintype "passive"))
      (node (ref "IC4") (pin "7") (pinfunction "QH_7") (pintype "tri_state"))
    )
    (net (code "66") (name "Net-(IC4A-SER)") (class "Default")
      (node (ref "IC4") (pin "14") (pinfunction "SER_14") (pintype "input"))
      (node (ref "IC5") (pin "9") (pinfunction "QH*_9") (pintype "tri_state"))
    )
    (net (code "67") (name "Net-(IC5A-QA)") (class "Default")
      (node (ref "D53") (pin "C") (pinfunction "C_C") (pintype "passive"))
      (node (ref "IC5") (pin "15") (pinfunction "QA_15") (pintype "tri_state"))
    )
    (net (code "68") (name "Net-(IC5A-QB)") (class "Default")
      (node (ref "D54") (pin "C") (pinfunction "C_C") (pintype "passive"))
      (node (ref "IC5") (pin "1") (pinfunction "QB_1") (pintype "tri_state"))
    )
    (net (code "69") (name "Net-(IC5A-QC)") (class "Default")
      (node (ref "D55") (pin "C") (pinfunction "C_C") (pintype "passive"))
      (node (ref "IC5") (pin "2") (pinfunction "QC_2") (pintype "tri_state"))
    )
    (net (code "70") (name "Net-(IC5A-QD)") (class "Default")
      (node (ref "D21") (pin "C") (pinfunction "C_C") (pintype "passive"))
      (node (ref "IC5") (pin "3") (pinfunction "QD_3") (pintype "tri_state"))
    )
    (net (code "71") (name "Net-(IC5A-QE)") (class "Default")
      (node (ref "D22") (pin "C") (pinfunction "C_C") (pintype "passive"))
      (node (ref "IC5") (pin "4") (pinfunction "QE_4") (pintype "tri_state"))
    )
    (net (code "72") (name "Net-(IC5A-QF)") (class "Default")
      (node (ref "D23") (pin "C") (pinfunction "C_C") (pintype "passive"))
      (node (ref "IC5") (pin "5") (pinfunction "QF_5") (pintype "tri_state"))
    )
    (net (code "73") (name "Net-(IC5A-QG)") (class "Default")
      (node (ref "D24") (pin "C") (pinfunction "C_C") (pintype "passive"))
      (node (ref "IC5") (pin "6") (pinfunction "QG_6") (pintype "tri_state"))
    )
    (net (code "74") (name "Net-(IC5A-QH)") (class "Default")
      (node (ref "D25") (pin "C") (pinfunction "C_C") (pintype "passive"))
      (node (ref "IC5") (pin "7") (pinfunction "QH_7") (pintype "tri_state"))
    )
    (net (code "75") (name "Net-(IC5A-SER)") (class "Default")
      (node (ref "IC5") (pin "14") (pinfunction "SER_14") (pintype "input"))
      (node (ref "IC6") (pin "9") (pinfunction "QH*_9") (pintype "tri_state"))
    )
    (net (code "76") (name "Net-(IC6A-QA)") (class "Default")
      (node (ref "D56") (pin "C") (pinfunction "C_C") (pintype "passive"))
      (node (ref "IC6") (pin "15") (pinfunction "QA_15") (pintype "tri_state"))
    )
    (net (code "77") (name "Net-(IC6A-QB)") (class "Default")
      (node (ref "D57") (pin "C") (pinfunction "C_C") (pintype "passive"))
      (node (ref "IC6") (pin "1") (pinfunction "QB_1") (pintype "tri_state"))
    )
    (net (code "78") (name "Net-(IC6A-QC)") (class "Default")
      (node (ref "D58") (pin "C") (pinfunction "C_C") (pintype "passive"))
      (node (ref "IC6") (pin "2") (pinfunction "QC_2") (pintype "tri_state"))
    )
    (net (code "79") (name "Net-(IC6A-QD)") (class "Default")
      (node (ref "D26") (pin "C") (pinfunction "C_C") (pintype "passive"))
      (node (ref "IC6") (pin "3") (pinfunction "QD_3") (pintype "tri_state"))
    )
    (net (code "80") (name "Net-(IC6A-QE)") (class "Default")
      (node (ref "D27") (pin "C") (pinfunction "C_C") (pintype "passive"))
      (node (ref "IC6") (pin "4") (pinfunction "QE_4") (pintype "tri_state"))
    )
    (net (code "81") (name "Net-(IC6A-QF)") (class "Default")
      (node (ref "D28") (pin "C") (pinfunction "C_C") (pintype "passive"))
      (node (ref "IC6") (pin "5") (pinfunction "QF_5") (pintype "tri_state"))
    )
    (net (code "82") (name "Net-(IC6A-QG)") (class "Default")
      (node (ref "D29") (pin "C") (pinfunction "C_C") (pintype "passive"))
      (node (ref "IC6") (pin "6") (pinfunction "QG_6") (pintype "tri_state"))
    )
    (net (code "83") (name "Net-(IC6A-QH)") (class "Default")
      (node (ref "D30") (pin "C") (pinfunction "C_C") (pintype "passive"))
      (node (ref "IC6") (pin "7") (pinfunction "QH_7") (pintype "tri_state"))
    )
    (net (code "84") (name "Net-(IC6A-SER)") (class "Default")
      (node (ref "IC6") (pin "14") (pinfunction "SER_14") (pintype "input"))
      (node (ref "IC7") (pin "9") (pinfunction "QH*_9") (pintype "tri_state"))
    )
    (net (code "85") (name "Net-(IC7A-QA)") (class "Default")
      (node (ref "D59") (pin "C") (pinfunction "C_C") (pintype "passive"))
      (node (ref "IC7") (pin "15") (pinfunction "QA_15") (pintype "tri_state"))
    )
    (net (code "86") (name "Net-(IC7A-QB)") (class "Default")
      (node (ref "D60") (pin "C") (pinfunction "C_C") (pintype "passive"))
      (node (ref "IC7") (pin "1") (pinfunction "QB_1") (pintype "tri_state"))
    )
    (net (code "87") (name "Net-(IC7A-QC)") (class "Default")
      (node (ref "D61") (pin "C") (pinfunction "C_C") (pintype "passive"))
      (node (ref "IC7") (pin "2") (pinfunction "QC_2") (pintype "tri_state"))
    )
    (net (code "88") (name "Net-(IC7A-QD)") (class "Default")
      (node (ref "D31") (pin "C") (pinfunction "C_C") (pintype "passive"))
      (node (ref "IC7") (pin "3") (pinfunction "QD_3") (pintype "tri_state"))
    )
    (net (code "89") (name "Net-(IC7A-QE)") (class "Default")
      (node (ref "D32") (pin "C") (pinfunction "C_C") (pintype "passive"))
      (node (ref "IC7") (pin "4") (pinfunction "QE_4") (pintype "tri_state"))
    )
    (net (code "90") (name "Net-(IC7A-QF)") (class "Default")
      (node (ref "D33") (pin "C") (pinfunction "C_C") (pintype "passive"))
      (node (ref "IC7") (pin "5") (pinfunction "QF_5") (pintype "tri_state"))
    )
    (net (code "91") (name "Net-(IC7A-QG)") (class "Default")
      (node (ref "D34") (pin "C") (pinfunction "C_C") (pintype "passive"))
      (node (ref "IC7") (pin "6") (pinfunction "QG_6") (pintype "tri_state"))
    )
    (net (code "92") (name "Net-(IC7A-QH)") (class "Default")
      (node (ref "D35") (pin "C") (pinfunction "C_C") (pintype "passive"))
      (node (ref "IC7") (pin "7") (pinfunction "QH_7") (pintype "tri_state"))
    )
    (net (code "93") (name "Net-(IC7A-SER)") (class "Default")
      (node (ref "IC7") (pin "14") (pinfunction "SER_14") (pintype "input"))
      (node (ref "IC8") (pin "9") (pinfunction "QH*_9") (pintype "tri_state"))
    )
    (net (code "94") (name "Net-(IC8A-QA)") (class "Default")
      (node (ref "D62") (pin "C") (pinfunction "C_C") (pintype "passive"))
      (node (ref "IC8") (pin "15") (pinfunction "QA_15") (pintype "tri_state"))
    )
    (net (code "95") (name "Net-(IC8A-QB)") (class "Default")
      (node (ref "D63") (pin "C") (pinfunction "C_C") (pintype "passive"))
      (node (ref "IC8") (pin "1") (pinfunction "QB_1") (pintype "tri_state"))
    )
    (net (code "96") (name "Net-(IC8A-QC)") (class "Default")
      (node (ref "D64") (pin "C") (pinfunction "C_C") (pintype "passive"))
      (node (ref "IC8") (pin "2") (pinfunction "QC_2") (pintype "tri_state"))
    )
    (net (code "97") (name "Net-(IC8A-QD)") (class "Default")
      (node (ref "D36") (pin "C") (pinfunction "C_C") (pintype "passive"))
      (node (ref "IC8") (pin "3") (pinfunction "QD_3") (pintype "tri_state"))
    )
    (net (code "98") (name "Net-(IC8A-QE)") (class "Default")
      (node (ref "D37") (pin "C") (pinfunction "C_C") (pintype "passive"))
      (node (ref "IC8") (pin "4") (pinfunction "QE_4") (pintype "tri_state"))
    )
    (net (code "99") (name "Net-(IC8A-QF)") (class "Default")
      (node (ref "D38") (pin "C") (pinfunction "C_C") (pintype "passive"))
      (node (ref "IC8") (pin "5") (pinfunction "QF_5") (pintype "tri_state"))
    )
    (net (code "100") (name "Net-(IC8A-QG)") (class "Default")
      (node (ref "D39") (pin "C") (pinfunction "C_C") (pintype "passive"))
      (node (ref "IC8") (pin "6") (pinfunction "QG_6") (pintype "tri_state"))
    )
    (net (code "101") (name "Net-(IC8A-QH)") (class "Default")
      (node (ref "D40") (pin "C") (pinfunction "C_C") (pintype "passive"))
      (node (ref "IC8") (pin "7") (pinfunction "QH_7") (pintype "tri_state"))
    )
    (net (code "102") (name "VCC") (class "Default")
      (node (ref "C1") (pin "1") (pinfunction "1_1") (pintype "passive"))
      (node (ref "C2") (pin "1") (pinfunction "1_1") (pintype "passive"))
      (node (ref "C3") (pin "1") (pinfunction "1_1") (pintype "passive"))
      (node (ref "C4") (pin "1") (pinfunction "1_1") (pintype "passive"))
      (node (ref "C5") (pin "+") (pinfunction "+_+") (pintype "passive"))
      (node (ref "IC1") (pin "10") (pinfunction "SCL_10") (pintype "input"))
      (node (ref "IC2") (pin "10") (pinfunction "SCL_10") (pintype "input"))
      (node (ref "IC3") (pin "10") (pinfunction "SCL_10") (pintype "input"))
      (node (ref "IC4") (pin "10") (pinfunction "SCL_10") (pintype "input"))
      (node (ref "IC5") (pin "10") (pinfunction "SCL_10") (pintype "input"))
      (node (ref "IC6") (pin "10") (pinfunction "SCL_10") (pintype "input"))
      (node (ref "IC7") (pin "10") (pinfunction "SCL_10") (pintype "input"))
      (node (ref "IC8") (pin "10") (pinfunction "SCL_10") (pintype "input"))
      (node (ref "IC9") (pin "1") (pinfunction "VDD_1") (pintype "power_in"))
      (node (ref "K1") (pin "4") (pinfunction "4_4") (pintype "passive"))
      (node (ref "K2") (pin "1") (pinfunction "1_1") (pintype "passive"))
      (node (ref "K3") (pin "1") (pinfunction "1_1") (pintype "passive"))
      (node (ref "K4") (pin "2") (pinfunction "2_2") (pintype "passive"))
      (node (ref "K5") (pin "2") (pinfunction "2_2") (pintype "passive"))
      (node (ref "R1") (pin "2") (pinfunction "2_2") (pintype "passive"))
      (node (ref "R10") (pin "2") (pinfunction "2_2") (pintype "passive"))
      (node (ref "R11") (pin "2") (pinfunction "2_2") (pintype "passive"))
      (node (ref "R2") (pin "2") (pinfunction "2_2") (pintype "passive"))
      (node (ref "R3") (pin "2") (pinfunction "2_2") (pintype "passive"))
      (node (ref "R4") (pin "2") (pinfunction "2_2") (pintype "passive"))
      (node (ref "R5") (pin "2") (pinfunction "2_2") (pintype "passive"))
      (node (ref "R6") (pin "2") (pinfunction "2_2") (pintype "passive"))
      (node (ref "R7") (pin "2") (pinfunction "2_2") (pintype "passive"))
      (node (ref "R8") (pin "2") (pinfunction "2_2") (pintype "passive"))
      (node (ref "R9") (pin "2") (pinfunction "2_2") (pintype "passive"))
      (node (ref "X1") (pin "1") (pinfunction "1_1") (pintype "passive"))
    )
    (net (code "103") (name "unconnected-(K1-Pad2)") (class "Default")
      (node (ref "K1") (pin "2") (pinfunction "2_2") (pintype "passive"))
    )
    (net (code "104") (name "unconnected-(K1-Pad6)") (class "Default")
      (node (ref "K1") (pin "6") (pinfunction "6_6") (pintype "passive"))
    )
  )
)
